# RPi-WS2812-HAT_v10.net
KiCad netlist of a schematic drawn in EAGLE
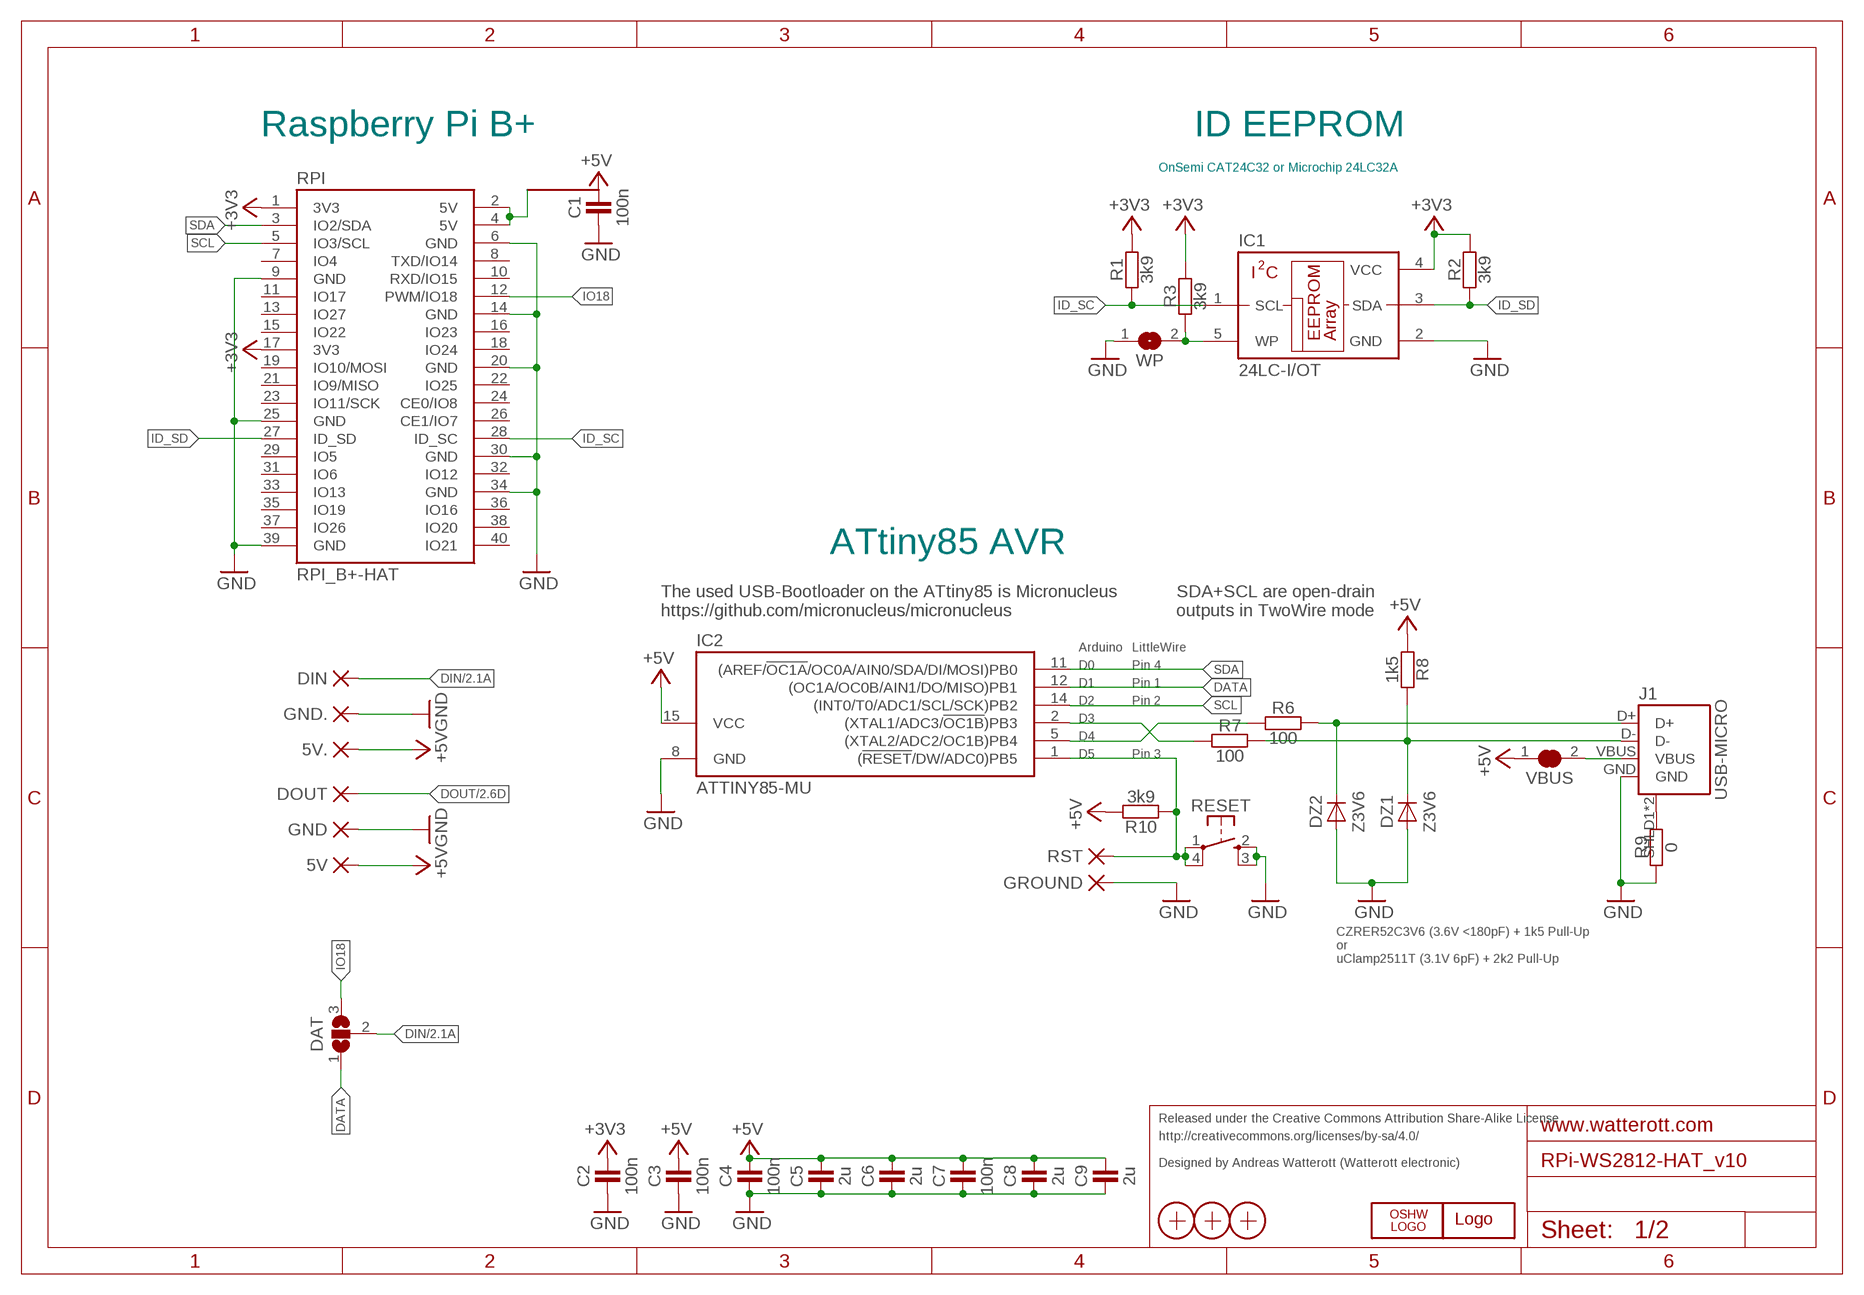
[diagram p0: schematic, sheet 1]
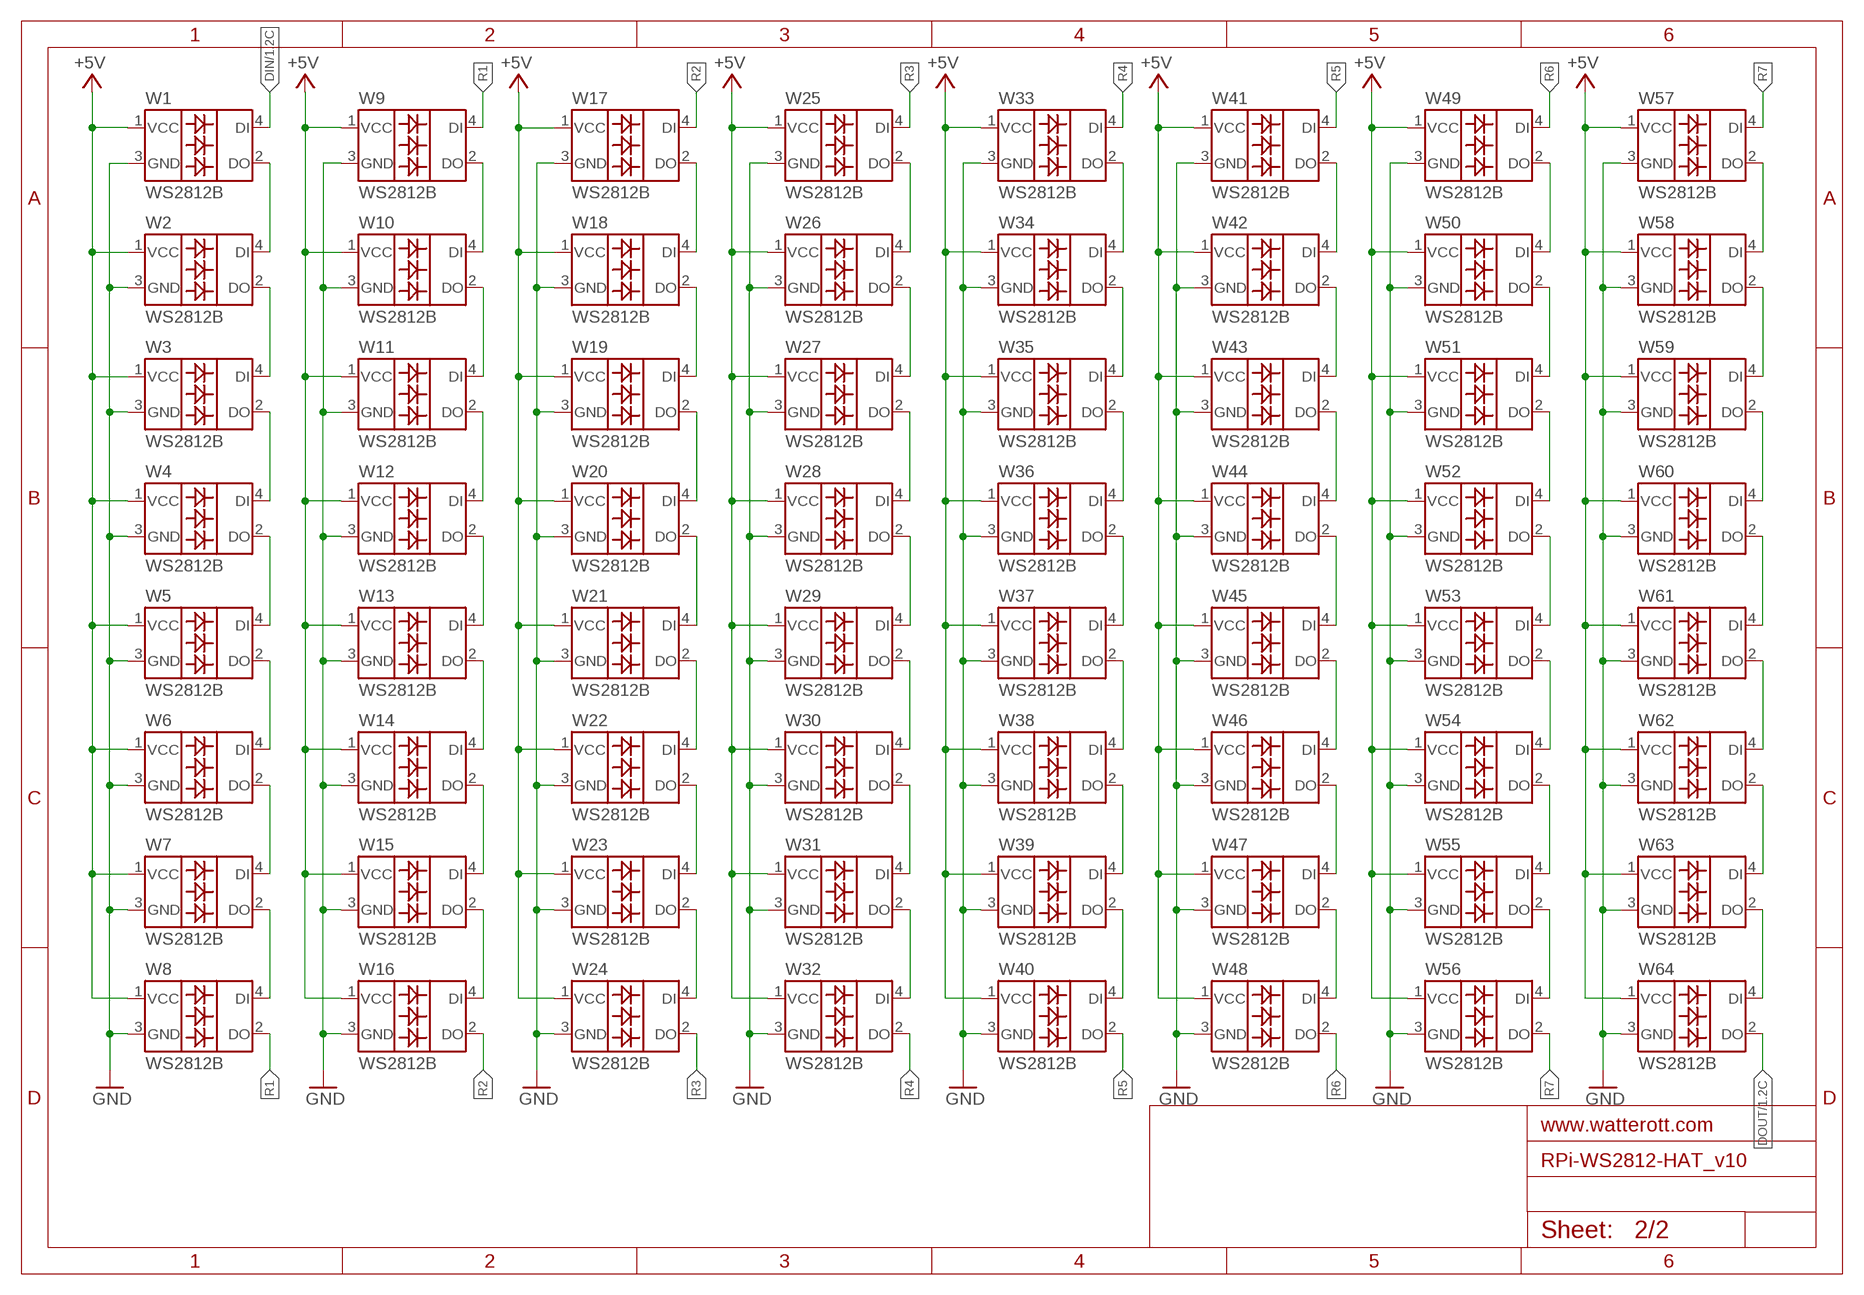
[diagram p1: schematic, sheet 2]

(export (version "E")
  (design (tool "Eeschema 10.0.6"))
  (components
    (comp (ref "W1")
      (value "WS2812B")
      (footprint "eagle-import:WS2812B")
      (libsource (lib "eagle-import") (part "WS2812B"))
    )
    (comp (ref "W2")
      (value "WS2812B")
      (footprint "eagle-import:WS2812B")
      (libsource (lib "eagle-import") (part "WS2812B"))
    )
    (comp (ref "W3")
      (value "WS2812B")
      (footprint "eagle-import:WS2812B")
      (libsource (lib "eagle-import") (part "WS2812B"))
    )
    (comp (ref "W4")
      (value "WS2812B")
      (footprint "eagle-import:WS2812B")
      (libsource (lib "eagle-import") (part "WS2812B"))
    )
    (comp (ref "W5")
      (value "WS2812B")
      (footprint "eagle-import:WS2812B")
      (libsource (lib "eagle-import") (part "WS2812B"))
    )
    (comp (ref "W6")
      (value "WS2812B")
      (footprint "eagle-import:WS2812B")
      (libsource (lib "eagle-import") (part "WS2812B"))
    )
    (comp (ref "W7")
      (value "WS2812B")
      (footprint "eagle-import:WS2812B")
      (libsource (lib "eagle-import") (part "WS2812B"))
    )
    (comp (ref "W8")
      (value "WS2812B")
      (footprint "eagle-import:WS2812B")
      (libsource (lib "eagle-import") (part "WS2812B"))
    )
    (comp (ref "W9")
      (value "WS2812B")
      (footprint "eagle-import:WS2812B")
      (libsource (lib "eagle-import") (part "WS2812B"))
    )
    (comp (ref "W10")
      (value "WS2812B")
      (footprint "eagle-import:WS2812B")
      (libsource (lib "eagle-import") (part "WS2812B"))
    )
    (comp (ref "W11")
      (value "WS2812B")
      (footprint "eagle-import:WS2812B")
      (libsource (lib "eagle-import") (part "WS2812B"))
    )
    (comp (ref "W12")
      (value "WS2812B")
      (footprint "eagle-import:WS2812B")
      (libsource (lib "eagle-import") (part "WS2812B"))
    )
    (comp (ref "W13")
      (value "WS2812B")
      (footprint "eagle-import:WS2812B")
      (libsource (lib "eagle-import") (part "WS2812B"))
    )
    (comp (ref "W14")
      (value "WS2812B")
      (footprint "eagle-import:WS2812B")
      (libsource (lib "eagle-import") (part "WS2812B"))
    )
    (comp (ref "W15")
      (value "WS2812B")
      (footprint "eagle-import:WS2812B")
      (libsource (lib "eagle-import") (part "WS2812B"))
    )
    (comp (ref "W16")
      (value "WS2812B")
      (footprint "eagle-import:WS2812B")
      (libsource (lib "eagle-import") (part "WS2812B"))
    )
    (comp (ref "W17")
      (value "WS2812B")
      (footprint "eagle-import:WS2812B")
      (libsource (lib "eagle-import") (part "WS2812B"))
    )
    (comp (ref "W18")
      (value "WS2812B")
      (footprint "eagle-import:WS2812B")
      (libsource (lib "eagle-import") (part "WS2812B"))
    )
    (comp (ref "W19")
      (value "WS2812B")
      (footprint "eagle-import:WS2812B")
      (libsource (lib "eagle-import") (part "WS2812B"))
    )
    (comp (ref "W20")
      (value "WS2812B")
      (footprint "eagle-import:WS2812B")
      (libsource (lib "eagle-import") (part "WS2812B"))
    )
    (comp (ref "W21")
      (value "WS2812B")
      (footprint "eagle-import:WS2812B")
      (libsource (lib "eagle-import") (part "WS2812B"))
    )
    (comp (ref "W22")
      (value "WS2812B")
      (footprint "eagle-import:WS2812B")
      (libsource (lib "eagle-import") (part "WS2812B"))
    )
    (comp (ref "W23")
      (value "WS2812B")
      (footprint "eagle-import:WS2812B")
      (libsource (lib "eagle-import") (part "WS2812B"))
    )
    (comp (ref "W24")
      (value "WS2812B")
      (footprint "eagle-import:WS2812B")
      (libsource (lib "eagle-import") (part "WS2812B"))
    )
    (comp (ref "W25")
      (value "WS2812B")
      (footprint "eagle-import:WS2812B")
      (libsource (lib "eagle-import") (part "WS2812B"))
    )
    (comp (ref "W26")
      (value "WS2812B")
      (footprint "eagle-import:WS2812B")
      (libsource (lib "eagle-import") (part "WS2812B"))
    )
    (comp (ref "W27")
      (value "WS2812B")
      (footprint "eagle-import:WS2812B")
      (libsource (lib "eagle-import") (part "WS2812B"))
    )
    (comp (ref "W28")
      (value "WS2812B")
      (footprint "eagle-import:WS2812B")
      (libsource (lib "eagle-import") (part "WS2812B"))
    )
    (comp (ref "W29")
      (value "WS2812B")
      (footprint "eagle-import:WS2812B")
      (libsource (lib "eagle-import") (part "WS2812B"))
    )
    (comp (ref "W30")
      (value "WS2812B")
      (footprint "eagle-import:WS2812B")
      (libsource (lib "eagle-import") (part "WS2812B"))
    )
    (comp (ref "W31")
      (value "WS2812B")
      (footprint "eagle-import:WS2812B")
      (libsource (lib "eagle-import") (part "WS2812B"))
    )
    (comp (ref "W32")
      (value "WS2812B")
      (footprint "eagle-import:WS2812B")
      (libsource (lib "eagle-import") (part "WS2812B"))
    )
    (comp (ref "W33")
      (value "WS2812B")
      (footprint "eagle-import:WS2812B")
      (libsource (lib "eagle-import") (part "WS2812B"))
    )
    (comp (ref "W34")
      (value "WS2812B")
      (footprint "eagle-import:WS2812B")
      (libsource (lib "eagle-import") (part "WS2812B"))
    )
    (comp (ref "W35")
      (value "WS2812B")
      (footprint "eagle-import:WS2812B")
      (libsource (lib "eagle-import") (part "WS2812B"))
    )
    (comp (ref "W36")
      (value "WS2812B")
      (footprint "eagle-import:WS2812B")
      (libsource (lib "eagle-import") (part "WS2812B"))
    )
    (comp (ref "W37")
      (value "WS2812B")
      (footprint "eagle-import:WS2812B")
      (libsource (lib "eagle-import") (part "WS2812B"))
    )
    (comp (ref "W38")
      (value "WS2812B")
      (footprint "eagle-import:WS2812B")
      (libsource (lib "eagle-import") (part "WS2812B"))
    )
    (comp (ref "W39")
      (value "WS2812B")
      (footprint "eagle-import:WS2812B")
      (libsource (lib "eagle-import") (part "WS2812B"))
    )
    (comp (ref "W40")
      (value "WS2812B")
      (footprint "eagle-import:WS2812B")
      (libsource (lib "eagle-import") (part "WS2812B"))
    )
    (comp (ref "W41")
      (value "WS2812B")
      (footprint "eagle-import:WS2812B")
      (libsource (lib "eagle-import") (part "WS2812B"))
    )
    (comp (ref "W42")
      (value "WS2812B")
      (footprint "eagle-import:WS2812B")
      (libsource (lib "eagle-import") (part "WS2812B"))
    )
    (comp (ref "W43")
      (value "WS2812B")
      (footprint "eagle-import:WS2812B")
      (libsource (lib "eagle-import") (part "WS2812B"))
    )
    (comp (ref "W44")
      (value "WS2812B")
      (footprint "eagle-import:WS2812B")
      (libsource (lib "eagle-import") (part "WS2812B"))
    )
    (comp (ref "W45")
      (value "WS2812B")
      (footprint "eagle-import:WS2812B")
      (libsource (lib "eagle-import") (part "WS2812B"))
    )
    (comp (ref "W46")
      (value "WS2812B")
      (footprint "eagle-import:WS2812B")
      (libsource (lib "eagle-import") (part "WS2812B"))
    )
    (comp (ref "W47")
      (value "WS2812B")
      (footprint "eagle-import:WS2812B")
      (libsource (lib "eagle-import") (part "WS2812B"))
    )
    (comp (ref "W48")
      (value "WS2812B")
      (footprint "eagle-import:WS2812B")
      (libsource (lib "eagle-import") (part "WS2812B"))
    )
    (comp (ref "W49")
      (value "WS2812B")
      (footprint "eagle-import:WS2812B")
      (libsource (lib "eagle-import") (part "WS2812B"))
    )
    (comp (ref "W50")
      (value "WS2812B")
      (footprint "eagle-import:WS2812B")
      (libsource (lib "eagle-import") (part "WS2812B"))
    )
    (comp (ref "W51")
      (value "WS2812B")
      (footprint "eagle-import:WS2812B")
      (libsource (lib "eagle-import") (part "WS2812B"))
    )
    (comp (ref "W52")
      (value "WS2812B")
      (footprint "eagle-import:WS2812B")
      (libsource (lib "eagle-import") (part "WS2812B"))
    )
    (comp (ref "W53")
      (value "WS2812B")
      (footprint "eagle-import:WS2812B")
      (libsource (lib "eagle-import") (part "WS2812B"))
    )
    (comp (ref "W54")
      (value "WS2812B")
      (footprint "eagle-import:WS2812B")
      (libsource (lib "eagle-import") (part "WS2812B"))
    )
    (comp (ref "W55")
      (value "WS2812B")
      (footprint "eagle-import:WS2812B")
      (libsource (lib "eagle-import") (part "WS2812B"))
    )
    (comp (ref "W56")
      (value "WS2812B")
      (footprint "eagle-import:WS2812B")
      (libsource (lib "eagle-import") (part "WS2812B"))
    )
    (comp (ref "W57")
      (value "WS2812B")
      (footprint "eagle-import:WS2812B")
      (libsource (lib "eagle-import") (part "WS2812B"))
    )
    (comp (ref "W58")
      (value "WS2812B")
      (footprint "eagle-import:WS2812B")
      (libsource (lib "eagle-import") (part "WS2812B"))
    )
    (comp (ref "W59")
      (value "WS2812B")
      (footprint "eagle-import:WS2812B")
      (libsource (lib "eagle-import") (part "WS2812B"))
    )
    (comp (ref "W60")
      (value "WS2812B")
      (footprint "eagle-import:WS2812B")
      (libsource (lib "eagle-import") (part "WS2812B"))
    )
    (comp (ref "W61")
      (value "WS2812B")
      (footprint "eagle-import:WS2812B")
      (libsource (lib "eagle-import") (part "WS2812B"))
    )
    (comp (ref "W62")
      (value "WS2812B")
      (footprint "eagle-import:WS2812B")
      (libsource (lib "eagle-import") (part "WS2812B"))
    )
    (comp (ref "W63")
      (value "WS2812B")
      (footprint "eagle-import:WS2812B")
      (libsource (lib "eagle-import") (part "WS2812B"))
    )
    (comp (ref "W64")
      (value "WS2812B")
      (footprint "eagle-import:WS2812B")
      (libsource (lib "eagle-import") (part "WS2812B"))
    )
    (comp (ref "5V")
      (value "PAD-1.27X2.54_NC")
      (footprint "eagle-import:PAD-1.27X2.54_NC")
      (libsource (lib "eagle-import") (part "PAD-1.27X2.54_NC"))
    )
    (comp (ref "5V.")
      (value "PAD-1.27X2.54_NC")
      (footprint "eagle-import:PAD-1.27X2.54_NC")
      (libsource (lib "eagle-import") (part "PAD-1.27X2.54_NC"))
    )
    (comp (ref "C1")
      (value "100n")
      (footprint "eagle-import:R0402")
      (libsource (lib "eagle-import") (part "CAPACITOR-C0402"))
    )
    (comp (ref "C2")
      (value "100n")
      (footprint "eagle-import:R0402")
      (libsource (lib "eagle-import") (part "CAPACITOR-C0402"))
    )
    (comp (ref "C3")
      (value "100n")
      (footprint "eagle-import:R0402")
      (libsource (lib "eagle-import") (part "CAPACITOR-C0402"))
    )
    (comp (ref "C4")
      (value "100n")
      (footprint "eagle-import:R0402")
      (libsource (lib "eagle-import") (part "CAPACITOR-C0402"))
    )
    (comp (ref "C5")
      (value "2u")
      (footprint "eagle-import:R0402")
      (libsource (lib "eagle-import") (part "CAPACITOR-C0402"))
    )
    (comp (ref "C6")
      (value "2u")
      (footprint "eagle-import:R0402")
      (libsource (lib "eagle-import") (part "CAPACITOR-C0402"))
    )
    (comp (ref "C7")
      (value "100n")
      (footprint "eagle-import:R0402")
      (libsource (lib "eagle-import") (part "CAPACITOR-C0402"))
    )
    (comp (ref "C8")
      (value "2u")
      (footprint "eagle-import:R0402")
      (libsource (lib "eagle-import") (part "CAPACITOR-C0402"))
    )
    (comp (ref "C9")
      (value "2u")
      (footprint "eagle-import:R0402")
      (libsource (lib "eagle-import") (part "CAPACITOR-C0402"))
    )
    (comp (ref "DAT")
      (value "JUMPER3-0603")
      (footprint "eagle-import:JUMPER3-0603")
      (libsource (lib "eagle-import") (part "JUMPER3-0603"))
    )
    (comp (ref "DIN")
      (value "PAD-1.27X2.54_NC")
      (footprint "eagle-import:PAD-1.27X2.54_NC")
      (libsource (lib "eagle-import") (part "PAD-1.27X2.54_NC"))
    )
    (comp (ref "DOUT")
      (value "PAD-1.27X2.54_NC")
      (footprint "eagle-import:PAD-1.27X2.54_NC")
      (libsource (lib "eagle-import") (part "PAD-1.27X2.54_NC"))
    )
    (comp (ref "DZ1")
      (value "Z3V6")
      (footprint "eagle-import:SOD882")
      (libsource (lib "eagle-import") (part "DIODE-SOD882"))
    )
    (comp (ref "DZ2")
      (value "Z3V6")
      (footprint "eagle-import:SOD882")
      (libsource (lib "eagle-import") (part "DIODE-SOD882"))
    )
    (comp (ref "GND")
      (value "PAD-1.27X2.54_NC")
      (footprint "eagle-import:PAD-1.27X2.54_NC")
      (libsource (lib "eagle-import") (part "PAD-1.27X2.54_NC"))
    )
    (comp (ref "GND.")
      (value "PAD-1.27X2.54_NC")
      (footprint "eagle-import:PAD-1.27X2.54_NC")
      (libsource (lib "eagle-import") (part "PAD-1.27X2.54_NC"))
    )
    (comp (ref "GROUND")
      (value "PAD-1.27X1.27_NC")
      (footprint "eagle-import:PAD-1.27X1.27_NC")
      (libsource (lib "eagle-import") (part "PAD-1.27X1.27_NC"))
    )
    (comp (ref "IC1")
      (value "24LC-I/OT")
      (footprint "eagle-import:SOT23-5")
      (libsource (lib "eagle-import") (part "24LC-I/OT"))
    )
    (comp (ref "IC2")
      (value "ATTINY85-MU")
      (footprint "eagle-import:QFN20-PAD")
      (libsource (lib "eagle-import") (part "ATTINY85-MU"))
    )
    (comp (ref "J1")
      (value "USB-MICRO")
      (footprint "eagle-import:USB-MICRO-10103594")
      (libsource (lib "eagle-import") (part "USB-MICRO"))
    )
    (comp (ref "LOGO1")
      (value "LOGO-S_PLACE_S")
      (footprint "eagle-import:SPARK_TPLACE_S")
      (libsource (lib "eagle-import") (part "LOGO-S_PLACE_S"))
    )
    (comp (ref "LOGO2")
      (value "OSHW_LOGOX0070")
      (footprint "eagle-import:OSHW_6X70")
      (libsource (lib "eagle-import") (part "OSHW_LOGOX0070"))
    )
    (comp (ref "R1")
      (value "3k9")
      (footprint "eagle-import:R0402")
      (libsource (lib "eagle-import") (part "RESISTOR-R0402"))
    )
    (comp (ref "R2")
      (value "3k9")
      (footprint "eagle-import:R0402")
      (libsource (lib "eagle-import") (part "RESISTOR-R0402"))
    )
    (comp (ref "R3")
      (value "3k9")
      (footprint "eagle-import:R0402")
      (libsource (lib "eagle-import") (part "RESISTOR-R0402"))
    )
    (comp (ref "R6")
      (value "100")
      (footprint "eagle-import:R0402")
      (libsource (lib "eagle-import") (part "RESISTOR-R0402"))
    )
    (comp (ref "R7")
      (value "100")
      (footprint "eagle-import:R0402")
      (libsource (lib "eagle-import") (part "RESISTOR-R0402"))
    )
    (comp (ref "R8")
      (value "1k5")
      (footprint "eagle-import:R0402")
      (libsource (lib "eagle-import") (part "RESISTOR-R0402"))
    )
    (comp (ref "R9")
      (value "0")
      (footprint "eagle-import:R0402")
      (libsource (lib "eagle-import") (part "RESISTOR-R0402"))
    )
    (comp (ref "R10")
      (value "3k9")
      (footprint "eagle-import:R0402")
      (libsource (lib "eagle-import") (part "RESISTOR-R0402"))
    )
    (comp (ref "RESET")
      (value "SW-TACTILE-TL3315")
      (footprint "eagle-import:SW_TL3315N")
      (libsource (lib "eagle-import") (part "SW-TACTILE-TL3315"))
    )
    (comp (ref "RPI")
      (value "RPI_B+-HAT")
      (footprint "eagle-import:RPI-B+HAT")
      (libsource (lib "eagle-import") (part "RPI_B+-HAT"))
    )
    (comp (ref "RST")
      (value "PAD-1.27X1.27_NC")
      (footprint "eagle-import:PAD-1.27X1.27_NC")
      (libsource (lib "eagle-import") (part "PAD-1.27X1.27_NC"))
    )
    (comp (ref "VBUS")
      (value "JUMPER2-0603-NC")
      (footprint "eagle-import:JUMPER2-0603_NC")
      (libsource (lib "eagle-import") (part "JUMPER2-0603-NC"))
    )
    (comp (ref "WP")
      (value "JUMPER2-0603-NC")
      (footprint "eagle-import:JUMPER2-0603_NC")
      (libsource (lib "eagle-import") (part "JUMPER2-0603-NC"))
    )
    (comp (ref "X1")
      (value "PASSER-07")
      (footprint "eagle-import:PASSER_07MM")
      (libsource (lib "eagle-import") (part "PASSER-07"))
    )
    (comp (ref "X2")
      (value "PASSER-07")
      (footprint "eagle-import:PASSER_07MM")
      (libsource (lib "eagle-import") (part "PASSER-07"))
    )
    (comp (ref "X3")
      (value "PASSER-07")
      (footprint "eagle-import:PASSER_07MM")
      (libsource (lib "eagle-import") (part "PASSER-07"))
    )
  )
  (nets
    (net (code "1") (name "+3V3") (class "Default")
      (node (ref "C2") (pin "2") (pinfunction "2_2") (pintype "passive"))
      (node (ref "IC1") (pin "4") (pinfunction "VCC_4") (pintype "power_in"))
      (node (ref "R1") (pin "2") (pinfunction "2_2") (pintype "passive"))
      (node (ref "R2") (pin "2") (pinfunction "2_2") (pintype "passive"))
      (node (ref "R3") (pin "2") (pinfunction "2_2") (pintype "passive"))
      (node (ref "RPI") (pin "1") (pinfunction "3V3_1") (pintype "passive"))
      (node (ref "RPI") (pin "17") (pinfunction "3V3_17") (pintype "passive"))
    )
    (net (code "2") (name "+5V") (class "Default")
      (node (ref "5V") (pin "1") (pinfunction "P_1") (pintype "passive"))
      (node (ref "5V.") (pin "1") (pinfunction "P_1") (pintype "passive"))
      (node (ref "C1") (pin "2") (pinfunction "2_2") (pintype "passive"))
      (node (ref "C3") (pin "2") (pinfunction "2_2") (pintype "passive"))
      (node (ref "C4") (pin "2") (pinfunction "2_2") (pintype "passive"))
      (node (ref "C5") (pin "2") (pinfunction "2_2") (pintype "passive"))
      (node (ref "C6") (pin "2") (pinfunction "2_2") (pintype "passive"))
      (node (ref "C7") (pin "2") (pinfunction "2_2") (pintype "passive"))
      (node (ref "C8") (pin "2") (pinfunction "2_2") (pintype "passive"))
      (node (ref "C9") (pin "2") (pinfunction "2_2") (pintype "passive"))
      (node (ref "IC2") (pin "15") (pinfunction "VCC_15") (pintype "power_in"))
      (node (ref "R10") (pin "2") (pinfunction "2_2") (pintype "passive"))
      (node (ref "R8") (pin "1") (pinfunction "1_1") (pintype "passive"))
      (node (ref "VBUS") (pin "1") (pinfunction "1_1") (pintype "passive"))
      (node (ref "W1") (pin "1") (pinfunction "VCC_1") (pintype "power_in"))
      (node (ref "W10") (pin "1") (pinfunction "VCC_1") (pintype "power_in"))
      (node (ref "W11") (pin "1") (pinfunction "VCC_1") (pintype "power_in"))
      (node (ref "W12") (pin "1") (pinfunction "VCC_1") (pintype "power_in"))
      (node (ref "W13") (pin "1") (pinfunction "VCC_1") (pintype "power_in"))
      (node (ref "W14") (pin "1") (pinfunction "VCC_1") (pintype "power_in"))
      (node (ref "W15") (pin "1") (pinfunction "VCC_1") (pintype "power_in"))
      (node (ref "W16") (pin "1") (pinfunction "VCC_1") (pintype "power_in"))
      (node (ref "W17") (pin "1") (pinfunction "VCC_1") (pintype "power_in"))
      (node (ref "W18") (pin "1") (pinfunction "VCC_1") (pintype "power_in"))
      (node (ref "W19") (pin "1") (pinfunction "VCC_1") (pintype "power_in"))
      (node (ref "W2") (pin "1") (pinfunction "VCC_1") (pintype "power_in"))
      (node (ref "W20") (pin "1") (pinfunction "VCC_1") (pintype "power_in"))
      (node (ref "W21") (pin "1") (pinfunction "VCC_1") (pintype "power_in"))
      (node (ref "W22") (pin "1") (pinfunction "VCC_1") (pintype "power_in"))
      (node (ref "W23") (pin "1") (pinfunction "VCC_1") (pintype "power_in"))
      (node (ref "W24") (pin "1") (pinfunction "VCC_1") (pintype "power_in"))
      (node (ref "W25") (pin "1") (pinfunction "VCC_1") (pintype "power_in"))
      (node (ref "W26") (pin "1") (pinfunction "VCC_1") (pintype "power_in"))
      (node (ref "W27") (pin "1") (pinfunction "VCC_1") (pintype "power_in"))
      (node (ref "W28") (pin "1") (pinfunction "VCC_1") (pintype "power_in"))
      (node (ref "W29") (pin "1") (pinfunction "VCC_1") (pintype "power_in"))
      (node (ref "W3") (pin "1") (pinfunction "VCC_1") (pintype "power_in"))
      (node (ref "W30") (pin "1") (pinfunction "VCC_1") (pintype "power_in"))
      (node (ref "W31") (pin "1") (pinfunction "VCC_1") (pintype "power_in"))
      (node (ref "W32") (pin "1") (pinfunction "VCC_1") (pintype "power_in"))
      (node (ref "W33") (pin "1") (pinfunction "VCC_1") (pintype "power_in"))
      (node (ref "W34") (pin "1") (pinfunction "VCC_1") (pintype "power_in"))
      (node (ref "W35") (pin "1") (pinfunction "VCC_1") (pintype "power_in"))
      (node (ref "W36") (pin "1") (pinfunction "VCC_1") (pintype "power_in"))
      (node (ref "W37") (pin "1") (pinfunction "VCC_1") (pintype "power_in"))
      (node (ref "W38") (pin "1") (pinfunction "VCC_1") (pintype "power_in"))
      (node (ref "W39") (pin "1") (pinfunction "VCC_1") (pintype "power_in"))
      (node (ref "W4") (pin "1") (pinfunction "VCC_1") (pintype "power_in"))
      (node (ref "W40") (pin "1") (pinfunction "VCC_1") (pintype "power_in"))
      (node (ref "W41") (pin "1") (pinfunction "VCC_1") (pintype "power_in"))
      (node (ref "W42") (pin "1") (pinfunction "VCC_1") (pintype "power_in"))
      (node (ref "W43") (pin "1") (pinfunction "VCC_1") (pintype "power_in"))
      (node (ref "W44") (pin "1") (pinfunction "VCC_1") (pintype "power_in"))
      (node (ref "W45") (pin "1") (pinfunction "VCC_1") (pintype "power_in"))
      (node (ref "W46") (pin "1") (pinfunction "VCC_1") (pintype "power_in"))
      (node (ref "W47") (pin "1") (pinfunction "VCC_1") (pintype "power_in"))
      (node (ref "W48") (pin "1") (pinfunction "VCC_1") (pintype "power_in"))
      (node (ref "W49") (pin "1") (pinfunction "VCC_1") (pintype "power_in"))
      (node (ref "W5") (pin "1") (pinfunction "VCC_1") (pintype "power_in"))
      (node (ref "W50") (pin "1") (pinfunction "VCC_1") (pintype "power_in"))
      (node (ref "W51") (pin "1") (pinfunction "VCC_1") (pintype "power_in"))
      (node (ref "W52") (pin "1") (pinfunction "VCC_1") (pintype "power_in"))
      (node (ref "W53") (pin "1") (pinfunction "VCC_1") (pintype "power_in"))
      (node (ref "W54") (pin "1") (pinfunction "VCC_1") (pintype "power_in"))
      (node (ref "W55") (pin "1") (pinfunction "VCC_1") (pintype "power_in"))
      (node (ref "W56") (pin "1") (pinfunction "VCC_1") (pintype "power_in"))
      (node (ref "W57") (pin "1") (pinfunction "VCC_1") (pintype "power_in"))
      (node (ref "W58") (pin "1") (pinfunction "VCC_1") (pintype "power_in"))
      (node (ref "W59") (pin "1") (pinfunction "VCC_1") (pintype "power_in"))
      (node (ref "W6") (pin "1") (pinfunction "VCC_1") (pintype "power_in"))
      (node (ref "W60") (pin "1") (pinfunction "VCC_1") (pintype "power_in"))
      (node (ref "W61") (pin "1") (pinfunction "VCC_1") (pintype "power_in"))
      (node (ref "W62") (pin "1") (pinfunction "VCC_1") (pintype "power_in"))
      (node (ref "W63") (pin "1") (pinfunction "VCC_1") (pintype "power_in"))
      (node (ref "W64") (pin "1") (pinfunction "VCC_1") (pintype "power_in"))
      (node (ref "W7") (pin "1") (pinfunction "VCC_1") (pintype "power_in"))
      (node (ref "W8") (pin "1") (pinfunction "VCC_1") (pintype "power_in"))
      (node (ref "W9") (pin "1") (pinfunction "VCC_1") (pintype "power_in"))
    )
    (net (code "3") (name "DATA") (class "Default")
      (node (ref "DAT") (pin "1") (pinfunction "1_1") (pintype "passive"))
      (node (ref "IC2") (pin "12") (pinfunction "(OC1A/OC0B/AIN1/DO/MISO)PB1_12") (pintype "bidirectional"))
    )
    (net (code "4") (name "DIN") (class "Default")
      (node (ref "DAT") (pin "2") (pinfunction "2_2") (pintype "passive"))
      (node (ref "DIN") (pin "1") (pinfunction "P_1") (pintype "passive"))
      (node (ref "W1") (pin "4") (pinfunction "DI_4") (pintype "bidirectional"))
    )
    (net (code "5") (name "DOUT") (class "Default")
      (node (ref "DOUT") (pin "1") (pinfunction "P_1") (pintype "passive"))
      (node (ref "W64") (pin "2") (pinfunction "DO_2") (pintype "bidirectional"))
    )
    (net (code "6") (name "GND") (class "Default")
      (node (ref "C1") (pin "1") (pinfunction "1_1") (pintype "passive"))
      (node (ref "C2") (pin "1") (pinfunction "1_1") (pintype "passive"))
      (node (ref "C3") (pin "1") (pinfunction "1_1") (pintype "passive"))
      (node (ref "C4") (pin "1") (pinfunction "1_1") (pintype "passive"))
      (node (ref "C5") (pin "1") (pinfunction "1_1") (pintype "passive"))
      (node (ref "C6") (pin "1") (pinfunction "1_1") (pintype "passive"))
      (node (ref "C7") (pin "1") (pinfunction "1_1") (pintype "passive"))
      (node (ref "C8") (pin "1") (pinfunction "1_1") (pintype "passive"))
      (node (ref "C9") (pin "1") (pinfunction "1_1") (pintype "passive"))
      (node (ref "DZ1") (pin "A") (pinfunction "A_A") (pintype "passive"))
      (node (ref "DZ2") (pin "A") (pinfunction "A_A") (pintype "passive"))
      (node (ref "GND") (pin "1") (pinfunction "P_1") (pintype "passive"))
      (node (ref "GND.") (pin "1") (pinfunction "P_1") (pintype "passive"))
      (node (ref "GROUND") (pin "1") (pinfunction "P_1") (pintype "passive"))
      (node (ref "IC1") (pin "2") (pinfunction "GND_2") (pintype "power_in"))
      (node (ref "IC2") (pin "8") (pinfunction "GND_8") (pintype "power_in"))
      (node (ref "J1") (pin "GND") (pinfunction "GND_GND") (pintype "power_in"))
      (node (ref "R9") (pin "1") (pinfunction "1_1") (pintype "passive"))
      (node (ref "RESET") (pin "2") (pinfunction "S1_2") (pintype "passive"))
      (node (ref "RESET") (pin "3") (pinfunction "S2_3") (pintype "passive"))
      (node (ref "RPI") (pin "14") (pinfunction "GND_14") (pintype "passive"))
      (node (ref "RPI") (pin "20") (pinfunction "GND_20") (pintype "passive"))
      (node (ref "RPI") (pin "25") (pinfunction "GND_25") (pintype "passive"))
      (node (ref "RPI") (pin "30") (pinfunction "GND_30") (pintype "bidirectional"))
      (node (ref "RPI") (pin "34") (pinfunction "GND_34") (pintype "bidirectional"))
      (node (ref "RPI") (pin "39") (pinfunction "GND_39") (pintype "bidirectional"))
      (node (ref "RPI") (pin "6") (pinfunction "GND_6") (pintype "passive"))
      (node (ref "RPI") (pin "9") (pinfunction "GND_9") (pintype "passive"))
      (node (ref "W1") (pin "3") (pinfunction "GND_3") (pintype "power_in"))
      (node (ref "W10") (pin "3") (pinfunction "GND_3") (pintype "power_in"))
      (node (ref "W11") (pin "3") (pinfunction "GND_3") (pintype "power_in"))
      (node (ref "W12") (pin "3") (pinfunction "GND_3") (pintype "power_in"))
      (node (ref "W13") (pin "3") (pinfunction "GND_3") (pintype "power_in"))
      (node (ref "W14") (pin "3") (pinfunction "GND_3") (pintype "power_in"))
      (node (ref "W15") (pin "3") (pinfunction "GND_3") (pintype "power_in"))
      (node (ref "W16") (pin "3") (pinfunction "GND_3") (pintype "power_in"))
      (node (ref "W17") (pin "3") (pinfunction "GND_3") (pintype "power_in"))
      (node (ref "W18") (pin "3") (pinfunction "GND_3") (pintype "power_in"))
      (node (ref "W19") (pin "3") (pinfunction "GND_3") (pintype "power_in"))
      (node (ref "W2") (pin "3") (pinfunction "GND_3") (pintype "power_in"))
      (node (ref "W20") (pin "3") (pinfunction "GND_3") (pintype "power_in"))
      (node (ref "W21") (pin "3") (pinfunction "GND_3") (pintype "power_in"))
      (node (ref "W22") (pin "3") (pinfunction "GND_3") (pintype "power_in"))
      (node (ref "W23") (pin "3") (pinfunction "GND_3") (pintype "power_in"))
      (node (ref "W24") (pin "3") (pinfunction "GND_3") (pintype "power_in"))
      (node (ref "W25") (pin "3") (pinfunction "GND_3") (pintype "power_in"))
      (node (ref "W26") (pin "3") (pinfunction "GND_3") (pintype "power_in"))
      (node (ref "W27") (pin "3") (pinfunction "GND_3") (pintype "power_in"))
      (node (ref "W28") (pin "3") (pinfunction "GND_3") (pintype "power_in"))
      (node (ref "W29") (pin "3") (pinfunction "GND_3") (pintype "power_in"))
      (node (ref "W3") (pin "3") (pinfunction "GND_3") (pintype "power_in"))
      (node (ref "W30") (pin "3") (pinfunction "GND_3") (pintype "power_in"))
      (node (ref "W31") (pin "3") (pinfunction "GND_3") (pintype "power_in"))
      (node (ref "W32") (pin "3") (pinfunction "GND_3") (pintype "power_in"))
      (node (ref "W33") (pin "3") (pinfunction "GND_3") (pintype "power_in"))
      (node (ref "W34") (pin "3") (pinfunction "GND_3") (pintype "power_in"))
      (node (ref "W35") (pin "3") (pinfunction "GND_3") (pintype "power_in"))
      (node (ref "W36") (pin "3") (pinfunction "GND_3") (pintype "power_in"))
      (node (ref "W37") (pin "3") (pinfunction "GND_3") (pintype "power_in"))
      (node (ref "W38") (pin "3") (pinfunction "GND_3") (pintype "power_in"))
      (node (ref "W39") (pin "3") (pinfunction "GND_3") (pintype "power_in"))
      (node (ref "W4") (pin "3") (pinfunction "GND_3") (pintype "power_in"))
      (node (ref "W40") (pin "3") (pinfunction "GND_3") (pintype "power_in"))
      (node (ref "W41") (pin "3") (pinfunction "GND_3") (pintype "power_in"))
      (node (ref "W42") (pin "3") (pinfunction "GND_3") (pintype "power_in"))
      (node (ref "W43") (pin "3") (pinfunction "GND_3") (pintype "power_in"))
      (node (ref "W44") (pin "3") (pinfunction "GND_3") (pintype "power_in"))
      (node (ref "W45") (pin "3") (pinfunction "GND_3") (pintype "power_in"))
      (node (ref "W46") (pin "3") (pinfunction "GND_3") (pintype "power_in"))
      (node (ref "W47") (pin "3") (pinfunction "GND_3") (pintype "power_in"))
      (node (ref "W48") (pin "3") (pinfunction "GND_3") (pintype "power_in"))
      (node (ref "W49") (pin "3") (pinfunction "GND_3") (pintype "power_in"))
      (node (ref "W5") (pin "3") (pinfunction "GND_3") (pintype "power_in"))
      (node (ref "W50") (pin "3") (pinfunction "GND_3") (pintype "power_in"))
      (node (ref "W51") (pin "3") (pinfunction "GND_3") (pintype "power_in"))
      (node (ref "W52") (pin "3") (pinfunction "GND_3") (pintype "power_in"))
      (node (ref "W53") (pin "3") (pinfunction "GND_3") (pintype "power_in"))
      (node (ref "W54") (pin "3") (pinfunction "GND_3") (pintype "power_in"))
      (node (ref "W55") (pin "3") (pinfunction "GND_3") (pintype "power_in"))
      (node (ref "W56") (pin "3") (pinfunction "GND_3") (pintype "power_in"))
      (node (ref "W57") (pin "3") (pinfunction "GND_3") (pintype "power_in"))
      (node (ref "W58") (pin "3") (pinfunction "GND_3") (pintype "power_in"))
      (node (ref "W59") (pin "3") (pinfunction "GND_3") (pintype "power_in"))
      (node (ref "W6") (pin "3") (pinfunction "GND_3") (pintype "power_in"))
      (node (ref "W60") (pin "3") (pinfunction "GND_3") (pintype "power_in"))
      (node (ref "W61") (pin "3") (pinfunction "GND_3") (pintype "power_in"))
      (node (ref "W62") (pin "3") (pinfunction "GND_3") (pintype "power_in"))
      (node (ref "W63") (pin "3") (pinfunction "GND_3") (pintype "power_in"))
      (node (ref "W64") (pin "3") (pinfunction "GND_3") (pintype "power_in"))
      (node (ref "W7") (pin "3") (pinfunction "GND_3") (pintype "power_in"))
      (node (ref "W8") (pin "3") (pinfunction "GND_3") (pintype "power_in"))
      (node (ref "W9") (pin "3") (pinfunction "GND_3") (pintype "power_in"))
      (node (ref "WP") (pin "1") (pinfunction "1_1") (pintype "passive"))
    )
    (net (code "7") (name "ID_SC") (class "Default")
      (node (ref "IC1") (pin "1") (pinfunction "SCL_1") (pintype "bidirectional"))
      (node (ref "R1") (pin "1") (pinfunction "1_1") (pintype "passive"))
      (node (ref "RPI") (pin "28") (pinfunction "ID_SC_28") (pintype "bidirectional"))
    )
    (net (code "8") (name "ID_SD") (class "Default")
      (node (ref "IC1") (pin "3") (pinfunction "SDA_3") (pintype "bidirectional"))
      (node (ref "R2") (pin "1") (pinfunction "1_1") (pintype "passive"))
      (node (ref "RPI") (pin "27") (pinfunction "ID_SD_27") (pintype "bidirectional"))
    )
    (net (code "9") (name "IO18") (class "Default")
      (node (ref "DAT") (pin "3") (pinfunction "3_3") (pintype "passive"))
      (node (ref "RPI") (pin "12") (pinfunction "PWM/IO18_12") (pintype "passive"))
    )
    (net (code "10") (name "Net-(DZ1-PadC)") (class "Default")
      (node (ref "DZ1") (pin "C") (pinfunction "C_C") (pintype "passive"))
      (node (ref "J1") (pin "D-") (pinfunction "D-_D-") (pintype "bidirectional"))
      (node (ref "R7") (pin "2") (pinfunction "2_2") (pintype "passive"))
      (node (ref "R8") (pin "2") (pinfunction "2_2") (pintype "passive"))
    )
    (net (code "11") (name "Net-(DZ2-PadC)") (class "Default")
      (node (ref "DZ2") (pin "C") (pinfunction "C_C") (pintype "passive"))
      (node (ref "J1") (pin "D+") (pinfunction "D+_D+") (pintype "bidirectional"))
      (node (ref "R6") (pin "2") (pinfunction "2_2") (pintype "passive"))
    )
    (net (code "12") (name "Net-(IC1-WP)") (class "Default")
      (node (ref "IC1") (pin "5") (pinfunction "WP_5") (pintype "bidirectional"))
      (node (ref "R3") (pin "1") (pinfunction "1_1") (pintype "passive"))
      (node (ref "WP") (pin "2") (pinfunction "2_2") (pintype "passive"))
    )
    (net (code "13") (name "Net-(IC2-(XTAL1{slash}ADC3{slash}~{OC1B})PB3)") (class "Default")
      (node (ref "IC2") (pin "2") (pinfunction "(XTAL1/ADC3/~{OC1B})PB3_2") (pintype "bidirectional"))
      (node (ref "R7") (pin "1") (pinfunction "1_1") (pintype "passive"))
    )
    (net (code "14") (name "Net-(IC2-(XTAL2{slash}ADC2{slash}OC1B)PB4)") (class "Default")
      (node (ref "IC2") (pin "5") (pinfunction "(XTAL2/ADC2/OC1B)PB4_5") (pintype "bidirectional"))
      (node (ref "R6") (pin "1") (pinfunction "1_1") (pintype "passive"))
    )
    (net (code "15") (name "Net-(IC2-(~{RESET}{slash}DW{slash}ADC0)PB5)") (class "Default")
      (node (ref "IC2") (pin "1") (pinfunction "(~{RESET}/DW/ADC0)PB5_1") (pintype "bidirectional"))
      (node (ref "R10") (pin "1") (pinfunction "1_1") (pintype "passive"))
      (node (ref "RESET") (pin "1") (pinfunction "P1_1") (pintype "passive"))
      (node (ref "RESET") (pin "4") (pinfunction "P2_4") (pintype "passive"))
      (node (ref "RST") (pin "1") (pinfunction "P_1") (pintype "passive"))
    )
    (net (code "16") (name "Net-(J1-PadVBUS)") (class "Default")
      (node (ref "J1") (pin "VBUS") (pinfunction "VBUS_VBUS") (pintype "power_in"))
      (node (ref "VBUS") (pin "2") (pinfunction "2_2") (pintype "passive"))
    )
    (net (code "17") (name "Net-(J1-SHIELD-PadSHLD1)") (class "Default")
      (node (ref "J1") (pin "SHLD1") (pinfunction "SHIELD_SHLD1") (pintype "passive"))
      (node (ref "J1") (pin "SHLD2") (pinfunction "SHIELD_SHLD2") (pintype "passive"))
      (node (ref "R9") (pin "2") (pinfunction "2_2") (pintype "passive"))
    )
    (net (code "18") (name "Net-(RPI-5V-Pad2)") (class "Default")
      (node (ref "RPI") (pin "2") (pinfunction "5V_2") (pintype "passive"))
      (node (ref "RPI") (pin "4") (pinfunction "5V_4") (pintype "passive"))
    )
    (net (code "19") (name "Net-(W1-DO)") (class "Default")
      (node (ref "W1") (pin "2") (pinfunction "DO_2") (pintype "bidirectional"))
      (node (ref "W2") (pin "4") (pinfunction "DI_4") (pintype "bidirectional"))
    )
    (net (code "20") (name "Net-(W2-DO)") (class "Default")
      (node (ref "W2") (pin "2") (pinfunction "DO_2") (pintype "bidirectional"))
      (node (ref "W3") (pin "4") (pinfunction "DI_4") (pintype "bidirectional"))
    )
    (net (code "21") (name "Net-(W3-DO)") (class "Default")
      (node (ref "W3") (pin "2") (pinfunction "DO_2") (pintype "bidirectional"))
      (node (ref "W4") (pin "4") (pinfunction "DI_4") (pintype "bidirectional"))
    )
    (net (code "22") (name "Net-(W4-DO)") (class "Default")
      (node (ref "W4") (pin "2") (pinfunction "DO_2") (pintype "bidirectional"))
      (node (ref "W5") (pin "4") (pinfunction "DI_4") (pintype "bidirectional"))
    )
    (net (code "23") (name "Net-(W5-DO)") (class "Default")
      (node (ref "W5") (pin "2") (pinfunction "DO_2") (pintype "bidirectional"))
      (node (ref "W6") (pin "4") (pinfunction "DI_4") (pintype "bidirectional"))
    )
    (net (code "24") (name "Net-(W6-DO)") (class "Default")
      (node (ref "W6") (pin "2") (pinfunction "DO_2") (pintype "bidirectional"))
      (node (ref "W7") (pin "4") (pinfunction "DI_4") (pintype "bidirectional"))
    )
    (net (code "25") (name "Net-(W7-DO)") (class "Default")
      (node (ref "W7") (pin "2") (pinfunction "DO_2") (pintype "bidirectional"))
      (node (ref "W8") (pin "4") (pinfunction "DI_4") (pintype "bidirectional"))
    )
    (net (code "26") (name "Net-(W10-DI)") (class "Default")
      (node (ref "W10") (pin "4") (pinfunction "DI_4") (pintype "bidirectional"))
      (node (ref "W9") (pin "2") (pinfunction "DO_2") (pintype "bidirectional"))
    )
    (net (code "27") (name "Net-(W10-DO)") (class "Default")
      (node (ref "W10") (pin "2") (pinfunction "DO_2") (pintype "bidirectional"))
      (node (ref "W11") (pin "4") (pinfunction "DI_4") (pintype "bidirectional"))
    )
    (net (code "28") (name "Net-(W11-DO)") (class "Default")
      (node (ref "W11") (pin "2") (pinfunction "DO_2") (pintype "bidirectional"))
      (node (ref "W12") (pin "4") (pinfunction "DI_4") (pintype "bidirectional"))
    )
    (net (code "29") (name "Net-(W12-DO)") (class "Default")
      (node (ref "W12") (pin "2") (pinfunction "DO_2") (pintype "bidirectional"))
      (node (ref "W13") (pin "4") (pinfunction "DI_4") (pintype "bidirectional"))
    )
    (net (code "30") (name "Net-(W13-DO)") (class "Default")
      (node (ref "W13") (pin "2") (pinfunction "DO_2") (pintype "bidirectional"))
      (node (ref "W14") (pin "4") (pinfunction "DI_4") (pintype "bidirectional"))
    )
    (net (code "31") (name "Net-(W14-DO)") (class "Default")
      (node (ref "W14") (pin "2") (pinfunction "DO_2") (pintype "bidirectional"))
      (node (ref "W15") (pin "4") (pinfunction "DI_4") (pintype "bidirectional"))
    )
    (net (code "32") (name "Net-(W15-DO)") (class "Default")
      (node (ref "W15") (pin "2") (pinfunction "DO_2") (pintype "bidirectional"))
      (node (ref "W16") (pin "4") (pinfunction "DI_4") (pintype "bidirectional"))
    )
    (net (code "33") (name "Net-(W17-DO)") (class "Default")
      (node (ref "W17") (pin "2") (pinfunction "DO_2") (pintype "bidirectional"))
      (node (ref "W18") (pin "4") (pinfunction "DI_4") (pintype "bidirectional"))
    )
    (net (code "34") (name "Net-(W18-DO)") (class "Default")
      (node (ref "W18") (pin "2") (pinfunction "DO_2") (pintype "bidirectional"))
      (node (ref "W19") (pin "4") (pinfunction "DI_4") (pintype "bidirectional"))
    )
    (net (code "35") (name "Net-(W19-DO)") (class "Default")
      (node (ref "W19") (pin "2") (pinfunction "DO_2") (pintype "bidirectional"))
      (node (ref "W20") (pin "4") (pinfunction "DI_4") (pintype "bidirectional"))
    )
    (net (code "36") (name "Net-(W20-DO)") (class "Default")
      (node (ref "W20") (pin "2") (pinfunction "DO_2") (pintype "bidirectional"))
      (node (ref "W21") (pin "4") (pinfunction "DI_4") (pintype "bidirectional"))
    )
    (net (code "37") (name "Net-(W21-DO)") (class "Default")
      (node (ref "W21") (pin "2") (pinfunction "DO_2") (pintype "bidirectional"))
      (node (ref "W22") (pin "4") (pinfunction "DI_4") (pintype "bidirectional"))
    )
    (net (code "38") (name "Net-(W22-DO)") (class "Default")
      (node (ref "W22") (pin "2") (pinfunction "DO_2") (pintype "bidirectional"))
      (node (ref "W23") (pin "4") (pinfunction "DI_4") (pintype "bidirectional"))
    )
    (net (code "39") (name "Net-(W23-DO)") (class "Default")
      (node (ref "W23") (pin "2") (pinfunction "DO_2") (pintype "bidirectional"))
      (node (ref "W24") (pin "4") (pinfunction "DI_4") (pintype "bidirectional"))
    )
    (net (code "40") (name "Net-(W25-DO)") (class "Default")
      (node (ref "W25") (pin "2") (pinfunction "DO_2") (pintype "bidirectional"))
      (node (ref "W26") (pin "4") (pinfunction "DI_4") (pintype "bidirectional"))
    )
    (net (code "41") (name "Net-(W26-DO)") (class "Default")
      (node (ref "W26") (pin "2") (pinfunction "DO_2") (pintype "bidirectional"))
      (node (ref "W27") (pin "4") (pinfunction "DI_4") (pintype "bidirectional"))
    )
    (net (code "42") (name "Net-(W27-DO)") (class "Default")
      (node (ref "W27") (pin "2") (pinfunction "DO_2") (pintype "bidirectional"))
      (node (ref "W28") (pin "4") (pinfunction "DI_4") (pintype "bidirectional"))
    )
    (net (code "43") (name "Net-(W28-DO)") (class "Default")
      (node (ref "W28") (pin "2") (pinfunction "DO_2") (pintype "bidirectional"))
      (node (ref "W29") (pin "4") (pinfunction "DI_4") (pintype "bidirectional"))
    )
    (net (code "44") (name "Net-(W29-DO)") (class "Default")
      (node (ref "W29") (pin "2") (pinfunction "DO_2") (pintype "bidirectional"))
      (node (ref "W30") (pin "4") (pinfunction "DI_4") (pintype "bidirectional"))
    )
    (net (code "45") (name "Net-(W30-DO)") (class "Default")
      (node (ref "W30") (pin "2") (pinfunction "DO_2") (pintype "bidirectional"))
      (node (ref "W31") (pin "4") (pinfunction "DI_4") (pintype "bidirectional"))
    )
    (net (code "46") (name "Net-(W31-DO)") (class "Default")
      (node (ref "W31") (pin "2") (pinfunction "DO_2") (pintype "bidirectional"))
      (node (ref "W32") (pin "4") (pinfunction "DI_4") (pintype "bidirectional"))
    )
    (net (code "47") (name "Net-(W33-DO)") (class "Default")
      (node (ref "W33") (pin "2") (pinfunction "DO_2") (pintype "bidirectional"))
      (node (ref "W34") (pin "4") (pinfunction "DI_4") (pintype "bidirectional"))
    )
    (net (code "48") (name "Net-(W34-DO)") (class "Default")
      (node (ref "W34") (pin "2") (pinfunction "DO_2") (pintype "bidirectional"))
      (node (ref "W35") (pin "4") (pinfunction "DI_4") (pintype "bidirectional"))
    )
    (net (code "49") (name "Net-(W35-DO)") (class "Default")
      (node (ref "W35") (pin "2") (pinfunction "DO_2") (pintype "bidirectional"))
      (node (ref "W36") (pin "4") (pinfunction "DI_4") (pintype "bidirectional"))
    )
    (net (code "50") (name "Net-(W36-DO)") (class "Default")
      (node (ref "W36") (pin "2") (pinfunction "DO_2") (pintype "bidirectional"))
      (node (ref "W37") (pin "4") (pinfunction "DI_4") (pintype "bidirectional"))
    )
    (net (code "51") (name "Net-(W37-DO)") (class "Default")
      (node (ref "W37") (pin "2") (pinfunction "DO_2") (pintype "bidirectional"))
      (node (ref "W38") (pin "4") (pinfunction "DI_4") (pintype "bidirectional"))
    )
    (net (code "52") (name "Net-(W38-DO)") (class "Default")
      (node (ref "W38") (pin "2") (pinfunction "DO_2") (pintype "bidirectional"))
      (node (ref "W39") (pin "4") (pinfunction "DI_4") (pintype "bidirectional"))
    )
    (net (code "53") (name "Net-(W39-DO)") (class "Default")
      (node (ref "W39") (pin "2") (pinfunction "DO_2") (pintype "bidirectional"))
      (node (ref "W40") (pin "4") (pinfunction "DI_4") (pintype "bidirectional"))
    )
    (net (code "54") (name "Net-(W41-DO)") (class "Default")
      (node (ref "W41") (pin "2") (pinfunction "DO_2") (pintype "bidirectional"))
      (node (ref "W42") (pin "4") (pinfunction "DI_4") (pintype "bidirectional"))
    )
    (net (code "55") (name "Net-(W42-DO)") (class "Default")
      (node (ref "W42") (pin "2") (pinfunction "DO_2") (pintype "bidirectional"))
      (node (ref "W43") (pin "4") (pinfunction "DI_4") (pintype "bidirectional"))
    )
    (net (code "56") (name "Net-(W43-DO)") (class "Default")
      (node (ref "W43") (pin "2") (pinfunction "DO_2") (pintype "bidirectional"))
      (node (ref "W44") (pin "4") (pinfunction "DI_4") (pintype "bidirectional"))
    )
    (net (code "57") (name "Net-(W44-DO)") (class "Default")
      (node (ref "W44") (pin "2") (pinfunction "DO_2") (pintype "bidirectional"))
      (node (ref "W45") (pin "4") (pinfunction "DI_4") (pintype "bidirectional"))
    )
    (net (code "58") (name "Net-(W45-DO)") (class "Default")
      (node (ref "W45") (pin "2") (pinfunction "DO_2") (pintype "bidirectional"))
      (node (ref "W46") (pin "4") (pinfunction "DI_4") (pintype "bidirectional"))
    )
    (net (code "59") (name "Net-(W46-DO)") (class "Default")
      (node (ref "W46") (pin "2") (pinfunction "DO_2") (pintype "bidirectional"))
      (node (ref "W47") (pin "4") (pinfunction "DI_4") (pintype "bidirectional"))
    )
    (net (code "60") (name "Net-(W47-DO)") (class "Default")
      (node (ref "W47") (pin "2") (pinfunction "DO_2") (pintype "bidirectional"))
      (node (ref "W48") (pin "4") (pinfunction "DI_4") (pintype "bidirectional"))
    )
    (net (code "61") (name "Net-(W49-DO)") (class "Default")
      (node (ref "W49") (pin "2") (pinfunction "DO_2") (pintype "bidirectional"))
      (node (ref "W50") (pin "4") (pinfunction "DI_4") (pintype "bidirectional"))
    )
    (net (code "62") (name "Net-(W50-DO)") (class "Default")
      (node (ref "W50") (pin "2") (pinfunction "DO_2") (pintype "bidirectional"))
      (node (ref "W51") (pin "4") (pinfunction "DI_4") (pintype "bidirectional"))
    )
    (net (code "63") (name "Net-(W51-DO)") (class "Default")
      (node (ref "W51") (pin "2") (pinfunction "DO_2") (pintype "bidirectional"))
      (node (ref "W52") (pin "4") (pinfunction "DI_4") (pintype "bidirectional"))
    )
    (net (code "64") (name "Net-(W52-DO)") (class "Default")
      (node (ref "W52") (pin "2") (pinfunction "DO_2") (pintype "bidirectional"))
      (node (ref "W53") (pin "4") (pinfunction "DI_4") (pintype "bidirectional"))
    )
    (net (code "65") (name "Net-(W53-DO)") (class "Default")
      (node (ref "W53") (pin "2") (pinfunction "DO_2") (pintype "bidirectional"))
      (node (ref "W54") (pin "4") (pinfunction "DI_4") (pintype "bidirectional"))
    )
    (net (code "66") (name "Net-(W54-DO)") (class "Default")
      (node (ref "W54") (pin "2") (pinfunction "DO_2") (pintype "bidirectional"))
      (node (ref "W55") (pin "4") (pinfunction "DI_4") (pintype "bidirectional"))
    )
    (net (code "67") (name "Net-(W55-DO)") (class "Default")
      (node (ref "W55") (pin "2") (pinfunction "DO_2") (pintype "bidirectional"))
      (node (ref "W56") (pin "4") (pinfunction "DI_4") (pintype "bidirectional"))
    )
    (net (code "68") (name "Net-(W57-DO)") (class "Default")
      (node (ref "W57") (pin "2") (pinfunction "DO_2") (pintype "bidirectional"))
      (node (ref "W58") (pin "4") (pinfunction "DI_4") (pintype "bidirectional"))
    )
    (net (code "69") (name "Net-(W58-DO)") (class "Default")
      (node (ref "W58") (pin "2") (pinfunction "DO_2") (pintype "bidirectional"))
      (node (ref "W59") (pin "4") (pinfunction "DI_4") (pintype "bidirectional"))
    )
    (net (code "70") (name "Net-(W59-DO)") (class "Default")
      (node (ref "W59") (pin "2") (pinfunction "DO_2") (pintype "bidirectional"))
      (node (ref "W60") (pin "4") (pinfunction "DI_4") (pintype "bidirectional"))
    )
    (net (code "71") (name "Net-(W60-DO)") (class "Default")
      (node (ref "W60") (pin "2") (pinfunction "DO_2") (pintype "bidirectional"))
      (node (ref "W61") (pin "4") (pinfunction "DI_4") (pintype "bidirectional"))
    )
    (net (code "72") (name "Net-(W61-DO)") (class "Default")
      (node (ref "W61") (pin "2") (pinfunction "DO_2") (pintype "bidirectional"))
      (node (ref "W62") (pin "4") (pinfunction "DI_4") (pintype "bidirectional"))
    )
    (net (code "73") (name "Net-(W62-DO)") (class "Default")
      (node (ref "W62") (pin "2") (pinfunction "DO_2") (pintype "bidirectional"))
      (node (ref "W63") (pin "4") (pinfunction "DI_4") (pintype "bidirectional"))
    )
    (net (code "74") (name "Net-(W63-DO)") (class "Default")
      (node (ref "W63") (pin "2") (pinfunction "DO_2") (pintype "bidirectional"))
      (node (ref "W64") (pin "4") (pinfunction "DI_4") (pintype "bidirectional"))
    )
    (net (code "75") (name "R1") (class "Default")
      (node (ref "W8") (pin "2") (pinfunction "DO_2") (pintype "bidirectional"))
      (node (ref "W9") (pin "4") (pinfunction "DI_4") (pintype "bidirectional"))
    )
    (net (code "76") (name "R2") (class "Default")
      (node (ref "W16") (pin "2") (pinfunction "DO_2") (pintype "bidirectional"))
      (node (ref "W17") (pin "4") (pinfunction "DI_4") (pintype "bidirectional"))
    )
    (net (code "77") (name "R3") (class "Default")
      (node (ref "W24") (pin "2") (pinfunction "DO_2") (pintype "bidirectional"))
      (node (ref "W25") (pin "4") (pinfunction "DI_4") (pintype "bidirectional"))
    )
    (net (code "78") (name "R4") (class "Default")
      (node (ref "W32") (pin "2") (pinfunction "DO_2") (pintype "bidirectional"))
      (node (ref "W33") (pin "4") (pinfunction "DI_4") (pintype "bidirectional"))
    )
    (net (code "79") (name "R5") (class "Default")
      (node (ref "W40") (pin "2") (pinfunction "DO_2") (pintype "bidirectional"))
      (node (ref "W41") (pin "4") (pinfunction "DI_4") (pintype "bidirectional"))
    )
    (net (code "80") (name "R6") (class "Default")
      (node (ref "W48") (pin "2") (pinfunction "DO_2") (pintype "bidirectional"))
      (node (ref "W49") (pin "4") (pinfunction "DI_4") (pintype "bidirectional"))
    )
    (net (code "81") (name "R7") (class "Default")
      (node (ref "W56") (pin "2") (pinfunction "DO_2") (pintype "bidirectional"))
      (node (ref "W57") (pin "4") (pinfunction "DI_4") (pintype "bidirectional"))
    )
    (net (code "82") (name "SCL") (class "Default")
      (node (ref "IC2") (pin "14") (pinfunction "(INT0/T0/ADC1/SCL/SCK)PB2_14") (pintype "bidirectional"))
      (node (ref "RPI") (pin "5") (pinfunction "IO3/SCL_5") (pintype "passive"))
    )
    (net (code "83") (name "SDA") (class "Default")
      (node (ref "IC2") (pin "11") (pinfunction "(AREF/~{OC1A}/OC0A/AIN0/SDA/DI/MOSI)PB0_11") (pintype "bidirectional"))
      (node (ref "RPI") (pin "3") (pinfunction "IO2/SDA_3") (pintype "passive"))
    )
    (net (code "84") (name "unconnected-(RPI-CE0{slash}IO8-Pad24)") (class "Default")
      (node (ref "RPI") (pin "24") (pinfunction "CE0/IO8_24") (pintype "passive"))
    )
    (net (code "85") (name "unconnected-(RPI-CE1{slash}IO7-Pad26)") (class "Default")
      (node (ref "RPI") (pin "26") (pinfunction "CE1/IO7_26") (pintype "passive"))
    )
    (net (code "86") (name "unconnected-(RPI-IO4-Pad7)") (class "Default")
      (node (ref "RPI") (pin "7") (pinfunction "IO4_7") (pintype "passive"))
    )
    (net (code "87") (name "unconnected-(RPI-IO5-Pad29)") (class "Default")
      (node (ref "RPI") (pin "29") (pinfunction "IO5_29") (pintype "bidirectional"))
    )
    (net (code "88") (name "unconnected-(RPI-IO6-Pad31)") (class "Default")
      (node (ref "RPI") (pin "31") (pinfunction "IO6_31") (pintype "bidirectional"))
    )
    (net (code "89") (name "unconnected-(RPI-IO9{slash}MISO-Pad21)") (class "Default")
      (node (ref "RPI") (pin "21") (pinfunction "IO9/MISO_21") (pintype "passive"))
    )
    (net (code "90") (name "unconnected-(RPI-IO10{slash}MOSI-Pad19)") (class "Default")
      (node (ref "RPI") (pin "19") (pinfunction "IO10/MOSI_19") (pintype "passive"))
    )
    (net (code "91") (name "unconnected-(RPI-IO11{slash}SCK-Pad23)") (class "Default")
      (node (ref "RPI") (pin "23") (pinfunction "IO11/SCK_23") (pintype "passive"))
    )
    (net (code "92") (name "unconnected-(RPI-IO12-Pad32)") (class "Default")
      (node (ref "RPI") (pin "32") (pinfunction "IO12_32") (pintype "bidirectional"))
    )
    (net (code "93") (name "unconnected-(RPI-IO13-Pad33)") (class "Default")
      (node (ref "RPI") (pin "33") (pinfunction "IO13_33") (pintype "bidirectional"))
    )
    (net (code "94") (name "unconnected-(RPI-IO16-Pad36)") (class "Default")
      (node (ref "RPI") (pin "36") (pinfunction "IO16_36") (pintype "bidirectional"))
    )
    (net (code "95") (name "unconnected-(RPI-IO17-Pad11)") (class "Default")
      (node (ref "RPI") (pin "11") (pinfunction "IO17_11") (pintype "passive"))
    )
    (net (code "96") (name "unconnected-(RPI-IO19-Pad35)") (class "Default")
      (node (ref "RPI") (pin "35") (pinfunction "IO19_35") (pintype "bidirectional"))
    )
    (net (code "97") (name "unconnected-(RPI-IO20-Pad38)") (class "Default")
      (node (ref "RPI") (pin "38") (pinfunction "IO20_38") (pintype "bidirectional"))
    )
    (net (code "98") (name "unconnected-(RPI-IO21-Pad40)") (class "Default")
      (node (ref "RPI") (pin "40") (pinfunction "IO21_40") (pintype "bidirectional"))
    )
    (net (code "99") (name "unconnected-(RPI-IO22-Pad15)") (class "Default")
      (node (ref "RPI") (pin "15") (pinfunction "IO22_15") (pintype "passive"))
    )
    (net (code "100") (name "unconnected-(RPI-IO23-Pad16)") (class "Default")
      (node (ref "RPI") (pin "16") (pinfunction "IO23_16") (pintype "passive"))
    )
    (net (code "101") (name "unconnected-(RPI-IO24-Pad18)") (class "Default")
      (node (ref "RPI") (pin "18") (pinfunction "IO24_18") (pintype "passive"))
    )
    (net (code "102") (name "unconnected-(RPI-IO25-Pad22)") (class "Default")
      (node (ref "RPI") (pin "22") (pinfunction "IO25_22") (pintype "passive"))
    )
    (net (code "103") (name "unconnected-(RPI-IO26-Pad37)") (class "Default")
      (node (ref "RPI") (pin "37") (pinfunction "IO26_37") (pintype "bidirectional"))
    )
    (net (code "104") (name "unconnected-(RPI-IO27-Pad13)") (class "Default")
      (node (ref "RPI") (pin "13") (pinfunction "IO27_13") (pintype "passive"))
    )
    (net (code "105") (name "unconnected-(RPI-RXD{slash}IO15-Pad10)") (class "Default")
      (node (ref "RPI") (pin "10") (pinfunction "RXD/IO15_10") (pintype "passive"))
    )
    (net (code "106") (name "unconnected-(RPI-TXD{slash}IO14-Pad8)") (class "Default")
      (node (ref "RPI") (pin "8") (pinfunction "TXD/IO14_8") (pintype "passive"))
    )
  )
)
